# S7CAS-PLEIADES-CARTE-MERE_P06_FPGA3.net
KiCad netlist of a schematic drawn in Altium Designer
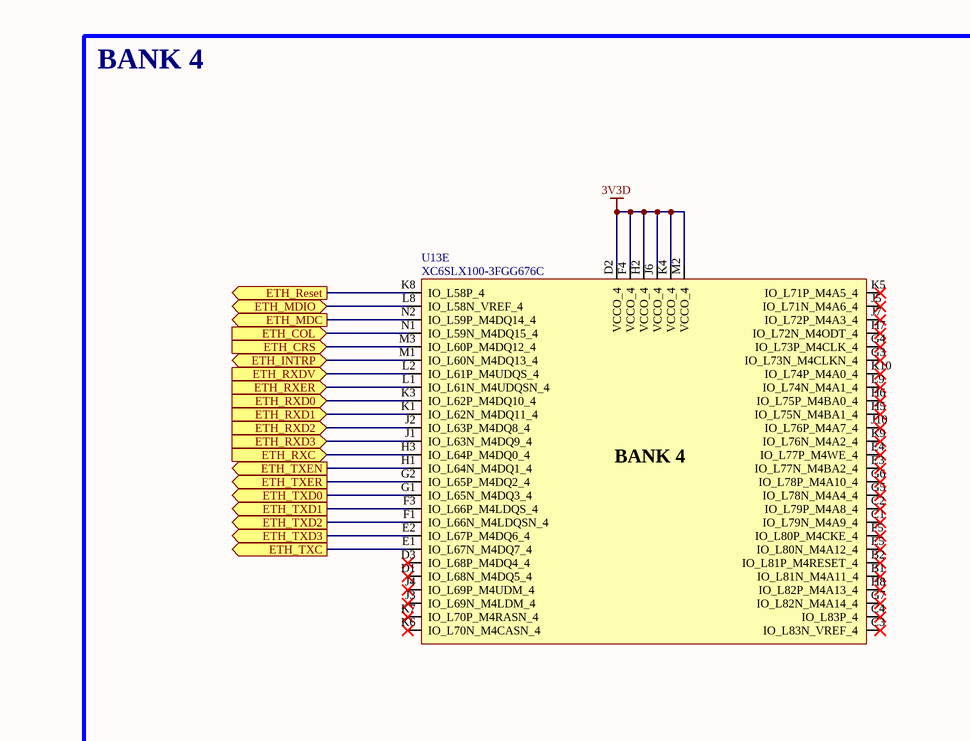
[diagram p0: S7CAS-PLEIADES-CARTE-MERE_P06_FPGA3.SCHDOC, top left]
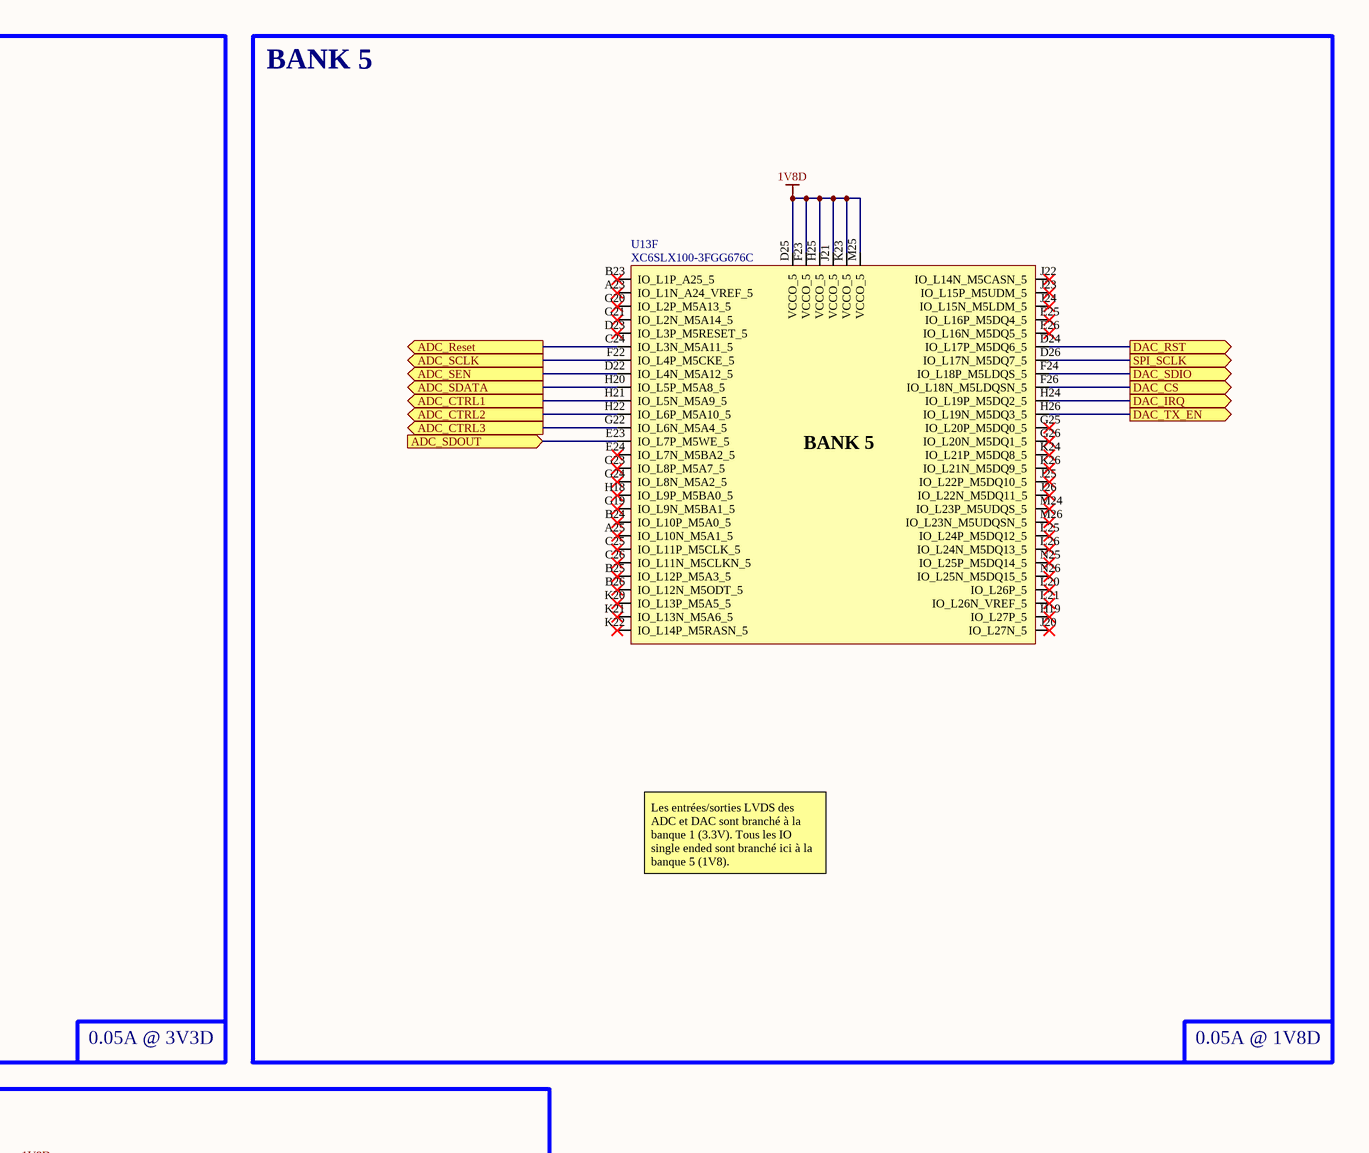
[diagram p1: S7CAS-PLEIADES-CARTE-MERE_P06_FPGA3.SCHDOC, top right]
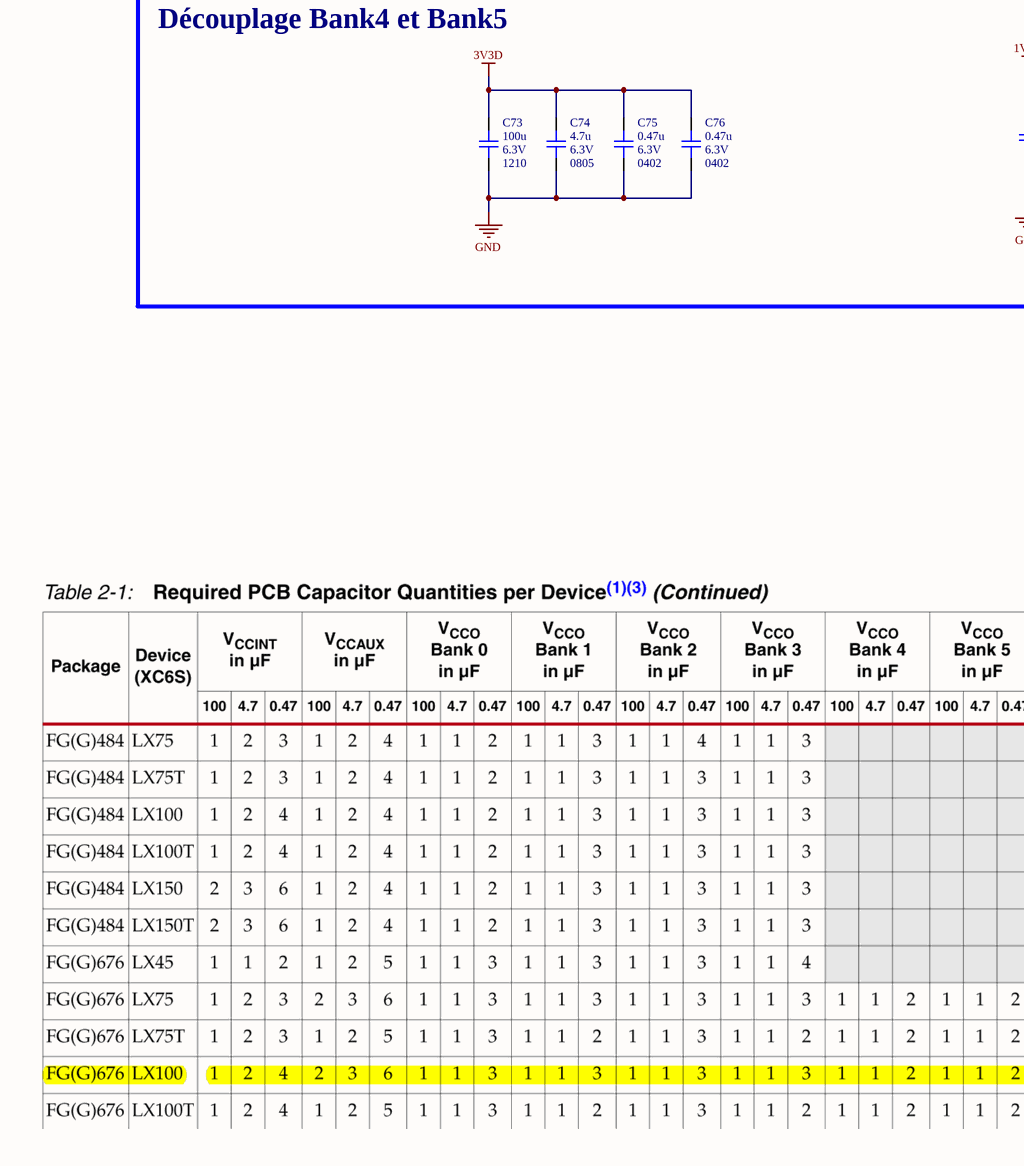
[diagram p2: S7CAS-PLEIADES-CARTE-MERE_P06_FPGA3.SCHDOC, bottom left]
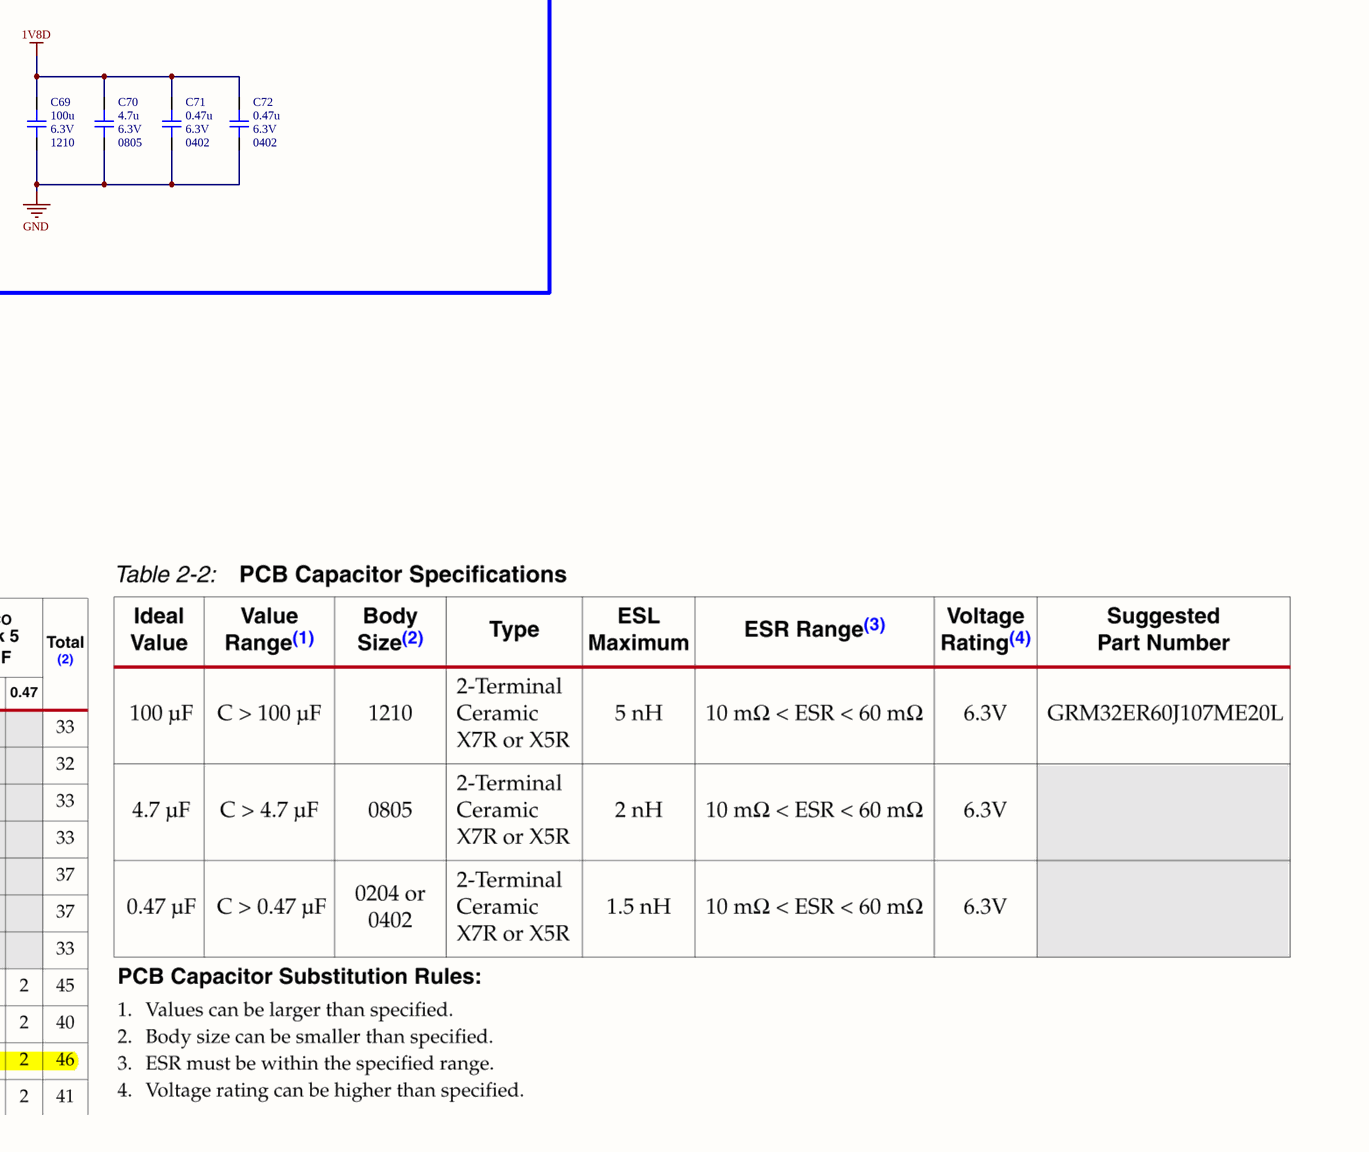
[diagram p3: S7CAS-PLEIADES-CARTE-MERE_P06_FPGA3.SCHDOC, bottom right]

(export (version "E")
  (design (tool "Eeschema 10.0.6"))
  (components
    (comp (ref "C69")
      (value "100u")
      (footprint "CAP_1210")
      (description "CAP - 1210")
      (fields
        (field (name "VOLTAGE") "6.3V")
        (field (name "PACKAGE") "1210")
        (field (name "CREATEDBY") "Jonathan Bouchard")
      )
      (libsource (lib "s7cas_lib2023") (part "CAP - 1210"))
    )
    (comp (ref "C70")
      (value "4.7u")
      (footprint "CAP_0805")
      (description "CAP - 0805")
      (fields
        (field (name "VOLTAGE") "6.3V")
        (field (name "PACKAGE") "0805")
        (field (name "CREATEDBY") "Jonathan Bouchard")
      )
      (libsource (lib "s7cas_lib2023") (part "CAP - 0805"))
    )
    (comp (ref "C71")
      (value "0.47u")
      (footprint "CAP_0402")
      (description "CAP - 0402")
      (fields
        (field (name "VOLTAGE") "6.3V")
        (field (name "PACKAGE") "0402")
        (field (name "CREATEDBY") "Jonathan Bouchard")
      )
      (libsource (lib "s7cas_lib2023") (part "CAP - 0402"))
    )
    (comp (ref "C72")
      (value "0.47u")
      (footprint "CAP_0402")
      (description "CAP - 0402")
      (fields
        (field (name "VOLTAGE") "6.3V")
        (field (name "PACKAGE") "0402")
        (field (name "CREATEDBY") "Jonathan Bouchard")
      )
      (libsource (lib "s7cas_lib2023") (part "CAP - 0402"))
    )
    (comp (ref "C73")
      (value "100u")
      (footprint "CAP_1210")
      (description "CAP - 1210")
      (fields
        (field (name "VOLTAGE") "6.3V")
        (field (name "PACKAGE") "1210")
        (field (name "CREATEDBY") "Jonathan Bouchard")
      )
      (libsource (lib "s7cas_lib2023") (part "CAP - 1210"))
    )
    (comp (ref "C74")
      (value "4.7u")
      (footprint "CAP_0805")
      (description "CAP - 0805")
      (fields
        (field (name "VOLTAGE") "6.3V")
        (field (name "PACKAGE") "0805")
        (field (name "CREATEDBY") "Jonathan Bouchard")
      )
      (libsource (lib "s7cas_lib2023") (part "CAP - 0805"))
    )
    (comp (ref "C75")
      (value "0.47u")
      (footprint "CAP_0402")
      (description "CAP - 0402")
      (fields
        (field (name "VOLTAGE") "6.3V")
        (field (name "PACKAGE") "0402")
        (field (name "CREATEDBY") "Jonathan Bouchard")
      )
      (libsource (lib "s7cas_lib2023") (part "CAP - 0402"))
    )
    (comp (ref "C76")
      (value "0.47u")
      (footprint "CAP_0402")
      (description "CAP - 0402")
      (fields
        (field (name "VOLTAGE") "6.3V")
        (field (name "PACKAGE") "0402")
        (field (name "CREATEDBY") "Jonathan Bouchard")
      )
      (libsource (lib "s7cas_lib2023") (part "CAP - 0402"))
    )
    (comp (ref "U13")
      (value "XC6SLX100-3FGG676C")
      (footprint "FPGA_XILINX_FGG676")
      (description "FPGA - XILINX SPARTAN 6 480 I/O - BGA-676")
      (fields
        (field (name "VOLTAGE") "1.14 V ~ 1.26 V")
        (field (name "MFG") "Xilinx")
        (field (name "CREATEDBY") "Jonathan Bouchard")
      )
      (libsource (lib "s7cas_lib2023") (part "FPGA_XC6SLX100-3FGG676C"))
    )
  )
  (nets
    (net (code "1") (name "/ADC_CTRL1") (class "Default")
      (node (ref "U13") (pin "H21") (pinfunction "IO_L5N_M5A9_5_H21") (pintype "passive"))
    )
    (net (code "2") (name "/ADC_CTRL2") (class "Default")
      (node (ref "U13") (pin "H22") (pinfunction "IO_L6P_M5A10_5_H22") (pintype "passive"))
    )
    (net (code "3") (name "/ADC_CTRL3") (class "Default")
      (node (ref "U13") (pin "G22") (pinfunction "IO_L6N_M5A4_5_G22") (pintype "passive"))
    )
    (net (code "4") (name "/ADC_Reset") (class "Default")
      (node (ref "U13") (pin "C24") (pinfunction "IO_L3N_M5A11_5_C24") (pintype "passive"))
    )
    (net (code "5") (name "/ADC_SCLK") (class "Default")
      (node (ref "U13") (pin "F22") (pinfunction "IO_L4P_M5CKE_5_F22") (pintype "passive"))
    )
    (net (code "6") (name "/ADC_SDATA") (class "Default")
      (node (ref "U13") (pin "H20") (pinfunction "IO_L5P_M5A8_5_H20") (pintype "passive"))
    )
    (net (code "7") (name "/ADC_SDOUT") (class "Default")
      (node (ref "U13") (pin "E23") (pinfunction "IO_L7P_M5WE_5_E23") (pintype "passive"))
    )
    (net (code "8") (name "/ADC_SEN") (class "Default")
      (node (ref "U13") (pin "D22") (pinfunction "IO_L4N_M5A12_5_D22") (pintype "passive"))
    )
    (net (code "9") (name "/DAC_CS") (class "Default")
      (node (ref "U13") (pin "F26") (pinfunction "IO_L18N_M5LDQSN_5_F26") (pintype "passive"))
    )
    (net (code "10") (name "/DAC_IRQ") (class "Default")
      (node (ref "U13") (pin "H24") (pinfunction "IO_L19P_M5DQ2_5_H24") (pintype "passive"))
    )
    (net (code "11") (name "/DAC_RST") (class "Default")
      (node (ref "U13") (pin "D24") (pinfunction "IO_L17P_M5DQ6_5_D24") (pintype "passive"))
    )
    (net (code "12") (name "/DAC_SDIO") (class "Default")
      (node (ref "U13") (pin "F24") (pinfunction "IO_L18P_M5LDQS_5_F24") (pintype "passive"))
    )
    (net (code "13") (name "/DAC_TX_EN") (class "Default")
      (node (ref "U13") (pin "H26") (pinfunction "IO_L19N_M5DQ3_5_H26") (pintype "passive"))
    )
    (net (code "14") (name "/ETH_COL") (class "Default")
      (node (ref "U13") (pin "N1") (pinfunction "IO_L59N_M4DQ15_4_N1") (pintype "passive"))
    )
    (net (code "15") (name "/ETH_CRS") (class "Default")
      (node (ref "U13") (pin "M3") (pinfunction "IO_L60P_M4DQ12_4_M3") (pintype "passive"))
    )
    (net (code "16") (name "/ETH_INTRP") (class "Default")
      (node (ref "U13") (pin "M1") (pinfunction "IO_L60N_M4DQ13_4_M1") (pintype "passive"))
    )
    (net (code "17") (name "/ETH_MDC") (class "Default")
      (node (ref "U13") (pin "N2") (pinfunction "IO_L59P_M4DQ14_4_N2") (pintype "passive"))
    )
    (net (code "18") (name "/ETH_MDIO") (class "Default")
      (node (ref "U13") (pin "L8") (pinfunction "IO_L58N_VREF_4_L8") (pintype "passive"))
    )
    (net (code "19") (name "/ETH_RXC") (class "Default")
      (node (ref "U13") (pin "H3") (pinfunction "IO_L64P_M4DQ0_4_H3") (pintype "passive"))
    )
    (net (code "20") (name "/ETH_RXD0") (class "Default")
      (node (ref "U13") (pin "K3") (pinfunction "IO_L62P_M4DQ10_4_K3") (pintype "passive"))
    )
    (net (code "21") (name "/ETH_RXD1") (class "Default")
      (node (ref "U13") (pin "K1") (pinfunction "IO_L62N_M4DQ11_4_K1") (pintype "passive"))
    )
    (net (code "22") (name "/ETH_RXD2") (class "Default")
      (node (ref "U13") (pin "J2") (pinfunction "IO_L63P_M4DQ8_4_J2") (pintype "passive"))
    )
    (net (code "23") (name "/ETH_RXD3") (class "Default")
      (node (ref "U13") (pin "J1") (pinfunction "IO_L63N_M4DQ9_4_J1") (pintype "passive"))
    )
    (net (code "24") (name "/ETH_RXDV") (class "Default")
      (node (ref "U13") (pin "L2") (pinfunction "IO_L61P_M4UDQS_4_L2") (pintype "passive"))
    )
    (net (code "25") (name "/ETH_RXER") (class "Default")
      (node (ref "U13") (pin "L1") (pinfunction "IO_L61N_M4UDQSN_4_L1") (pintype "passive"))
    )
    (net (code "26") (name "/ETH_Reset") (class "Default")
      (node (ref "U13") (pin "K8") (pinfunction "IO_L58P_4_K8") (pintype "passive"))
    )
    (net (code "27") (name "/ETH_TXC") (class "Default")
      (node (ref "U13") (pin "E1") (pinfunction "IO_L67N_M4DQ7_4_E1") (pintype "passive"))
    )
    (net (code "28") (name "/ETH_TXD0") (class "Default")
      (node (ref "U13") (pin "G1") (pinfunction "IO_L65N_M4DQ3_4_G1") (pintype "passive"))
    )
    (net (code "29") (name "/ETH_TXD1") (class "Default")
      (node (ref "U13") (pin "F3") (pinfunction "IO_L66P_M4LDQS_4_F3") (pintype "passive"))
    )
    (net (code "30") (name "/ETH_TXD2") (class "Default")
      (node (ref "U13") (pin "F1") (pinfunction "IO_L66N_M4LDQSN_4_F1") (pintype "passive"))
    )
    (net (code "31") (name "/ETH_TXD3") (class "Default")
      (node (ref "U13") (pin "E2") (pinfunction "IO_L67P_M4DQ6_4_E2") (pintype "passive"))
    )
    (net (code "32") (name "/ETH_TXEN") (class "Default")
      (node (ref "U13") (pin "H1") (pinfunction "IO_L64N_M4DQ1_4_H1") (pintype "passive"))
    )
    (net (code "33") (name "/ETH_TXER") (class "Default")
      (node (ref "U13") (pin "G2") (pinfunction "IO_L65P_M4DQ2_4_G2") (pintype "passive"))
    )
    (net (code "34") (name "/SPI_SCLK") (class "Default")
      (node (ref "U13") (pin "D26") (pinfunction "IO_L17N_M5DQ7_5_D26") (pintype "passive"))
    )
    (net (code "35") (name "1V8D") (class "Default")
      (node (ref "C69") (pin "2") (pinfunction "2_2") (pintype "passive"))
      (node (ref "C70") (pin "2") (pinfunction "2_2") (pintype "passive"))
      (node (ref "C71") (pin "2") (pinfunction "2_2") (pintype "passive"))
      (node (ref "C72") (pin "2") (pinfunction "2_2") (pintype "passive"))
      (node (ref "U13") (pin "D25") (pinfunction "VCCO_5_D25") (pintype "passive"))
      (node (ref "U13") (pin "F23") (pinfunction "VCCO_5_F23") (pintype "passive"))
      (node (ref "U13") (pin "H25") (pinfunction "VCCO_5_H25") (pintype "passive"))
      (node (ref "U13") (pin "J21") (pinfunction "VCCO_5_J21") (pintype "passive"))
      (node (ref "U13") (pin "K23") (pinfunction "VCCO_5_K23") (pintype "passive"))
      (node (ref "U13") (pin "M25") (pinfunction "VCCO_5_M25") (pintype "passive"))
    )
    (net (code "36") (name "3V3D") (class "Default")
      (node (ref "C73") (pin "2") (pinfunction "2_2") (pintype "passive"))
      (node (ref "C74") (pin "2") (pinfunction "2_2") (pintype "passive"))
      (node (ref "C75") (pin "2") (pinfunction "2_2") (pintype "passive"))
      (node (ref "C76") (pin "2") (pinfunction "2_2") (pintype "passive"))
      (node (ref "U13") (pin "D2") (pinfunction "VCCO_4_D2") (pintype "passive"))
      (node (ref "U13") (pin "F4") (pinfunction "VCCO_4_F4") (pintype "passive"))
      (node (ref "U13") (pin "H2") (pinfunction "VCCO_4_H2") (pintype "passive"))
      (node (ref "U13") (pin "J6") (pinfunction "VCCO_4_J6") (pintype "passive"))
      (node (ref "U13") (pin "K4") (pinfunction "VCCO_4_K4") (pintype "passive"))
      (node (ref "U13") (pin "M2") (pinfunction "VCCO_4_M2") (pintype "passive"))
    )
    (net (code "37") (name "GND") (class "Default")
      (node (ref "C69") (pin "1") (pinfunction "1_1") (pintype "passive"))
      (node (ref "C70") (pin "1") (pinfunction "1_1") (pintype "passive"))
      (node (ref "C71") (pin "1") (pinfunction "1_1") (pintype "passive"))
      (node (ref "C72") (pin "1") (pinfunction "1_1") (pintype "passive"))
      (node (ref "C73") (pin "1") (pinfunction "1_1") (pintype "passive"))
      (node (ref "C74") (pin "1") (pinfunction "1_1") (pintype "passive"))
      (node (ref "C75") (pin "1") (pinfunction "1_1") (pintype "passive"))
      (node (ref "C76") (pin "1") (pinfunction "1_1") (pintype "passive"))
    )
    (net (code "38") (name "unconnected-(U13E-IO_L68N_M4DQ5_4-PadD1)") (class "Default")
      (node (ref "U13") (pin "D1") (pinfunction "IO_L68N_M4DQ5_4_D1") (pintype "passive+no_connect"))
    )
    (net (code "39") (name "unconnected-(U13E-IO_L68P_M4DQ4_4-PadD3)") (class "Default")
      (node (ref "U13") (pin "D3") (pinfunction "IO_L68P_M4DQ4_4_D3") (pintype "passive+no_connect"))
    )
    (net (code "40") (name "unconnected-(U13E-IO_L69N_M4LDM_4-PadJ3)") (class "Default")
      (node (ref "U13") (pin "J3") (pinfunction "IO_L69N_M4LDM_4_J3") (pintype "passive+no_connect"))
    )
    (net (code "41") (name "unconnected-(U13E-IO_L69P_M4UDM_4-PadJ4)") (class "Default")
      (node (ref "U13") (pin "J4") (pinfunction "IO_L69P_M4UDM_4_J4") (pintype "passive+no_connect"))
    )
    (net (code "42") (name "unconnected-(U13E-IO_L70N_M4CASN_4-PadK6)") (class "Default")
      (node (ref "U13") (pin "K6") (pinfunction "IO_L70N_M4CASN_4_K6") (pintype "passive+no_connect"))
    )
    (net (code "43") (name "unconnected-(U13E-IO_L70P_M4RASN_4-PadK7)") (class "Default")
      (node (ref "U13") (pin "K7") (pinfunction "IO_L70P_M4RASN_4_K7") (pintype "passive+no_connect"))
    )
    (net (code "44") (name "unconnected-(U13E-IO_L71N_M4A6_4-PadJ5)") (class "Default")
      (node (ref "U13") (pin "J5") (pinfunction "IO_L71N_M4A6_4_J5") (pintype "passive+no_connect"))
    )
    (net (code "45") (name "unconnected-(U13E-IO_L71P_M4A5_4-PadK5)") (class "Default")
      (node (ref "U13") (pin "K5") (pinfunction "IO_L71P_M4A5_4_K5") (pintype "passive+no_connect"))
    )
    (net (code "46") (name "unconnected-(U13E-IO_L72N_M4ODT_4-PadH7)") (class "Default")
      (node (ref "U13") (pin "H7") (pinfunction "IO_L72N_M4ODT_4_H7") (pintype "passive+no_connect"))
    )
    (net (code "47") (name "unconnected-(U13E-IO_L72P_M4A3_4-PadJ7)") (class "Default")
      (node (ref "U13") (pin "J7") (pinfunction "IO_L72P_M4A3_4_J7") (pintype "passive+no_connect"))
    )
    (net (code "48") (name "unconnected-(U13E-IO_L73N_M4CLKN_4-PadG3)") (class "Default")
      (node (ref "U13") (pin "G3") (pinfunction "IO_L73N_M4CLKN_4_G3") (pintype "passive+no_connect"))
    )
    (net (code "49") (name "unconnected-(U13E-IO_L73P_M4CLK_4-PadG4)") (class "Default")
      (node (ref "U13") (pin "G4") (pinfunction "IO_L73P_M4CLK_4_G4") (pintype "passive+no_connect"))
    )
    (net (code "50") (name "unconnected-(U13E-IO_L74N_M4A1_4-PadL9)") (class "Default")
      (node (ref "U13") (pin "L9") (pinfunction "IO_L74N_M4A1_4_L9") (pintype "passive+no_connect"))
    )
    (net (code "51") (name "unconnected-(U13E-IO_L74P_M4A0_4-PadK10)") (class "Default")
      (node (ref "U13") (pin "K10") (pinfunction "IO_L74P_M4A0_4_K10") (pintype "passive+no_connect"))
    )
    (net (code "52") (name "unconnected-(U13E-IO_L75N_M4BA1_4-PadH5)") (class "Default")
      (node (ref "U13") (pin "H5") (pinfunction "IO_L75N_M4BA1_4_H5") (pintype "passive+no_connect"))
    )
    (net (code "53") (name "unconnected-(U13E-IO_L75P_M4BA0_4-PadH6)") (class "Default")
      (node (ref "U13") (pin "H6") (pinfunction "IO_L75P_M4BA0_4_H6") (pintype "passive+no_connect"))
    )
    (net (code "54") (name "unconnected-(U13E-IO_L76N_M4A2_4-PadK9)") (class "Default")
      (node (ref "U13") (pin "K9") (pinfunction "IO_L76N_M4A2_4_K9") (pintype "passive+no_connect"))
    )
    (net (code "55") (name "unconnected-(U13E-IO_L76P_M4A7_4-PadJ10)") (class "Default")
      (node (ref "U13") (pin "J10") (pinfunction "IO_L76P_M4A7_4_J10") (pintype "passive+no_connect"))
    )
    (net (code "56") (name "unconnected-(U13E-IO_L77N_M4BA2_4-PadE3)") (class "Default")
      (node (ref "U13") (pin "E3") (pinfunction "IO_L77N_M4BA2_4_E3") (pintype "passive+no_connect"))
    )
    (net (code "57") (name "unconnected-(U13E-IO_L77P_M4WE_4-PadE4)") (class "Default")
      (node (ref "U13") (pin "E4") (pinfunction "IO_L77P_M4WE_4_E4") (pintype "passive+no_connect"))
    )
    (net (code "58") (name "unconnected-(U13E-IO_L78N_M4A4_4-PadG5)") (class "Default")
      (node (ref "U13") (pin "G5") (pinfunction "IO_L78N_M4A4_4_G5") (pintype "passive+no_connect"))
    )
    (net (code "59") (name "unconnected-(U13E-IO_L78P_M4A10_4-PadG6)") (class "Default")
      (node (ref "U13") (pin "G6") (pinfunction "IO_L78P_M4A10_4_G6") (pintype "passive+no_connect"))
    )
    (net (code "60") (name "unconnected-(U13E-IO_L79N_M4A9_4-PadC1)") (class "Default")
      (node (ref "U13") (pin "C1") (pinfunction "IO_L79N_M4A9_4_C1") (pintype "passive+no_connect"))
    )
    (net (code "61") (name "unconnected-(U13E-IO_L79P_M4A8_4-PadC2)") (class "Default")
      (node (ref "U13") (pin "C2") (pinfunction "IO_L79P_M4A8_4_C2") (pintype "passive+no_connect"))
    )
    (net (code "62") (name "unconnected-(U13E-IO_L80N_M4A12_4-PadE5)") (class "Default")
      (node (ref "U13") (pin "E5") (pinfunction "IO_L80N_M4A12_4_E5") (pintype "passive+no_connect"))
    )
    (net (code "63") (name "unconnected-(U13E-IO_L80P_M4CKE_4-PadF5)") (class "Default")
      (node (ref "U13") (pin "F5") (pinfunction "IO_L80P_M4CKE_4_F5") (pintype "passive+no_connect"))
    )
    (net (code "64") (name "unconnected-(U13E-IO_L81N_M4A11_4-PadB1)") (class "Default")
      (node (ref "U13") (pin "B1") (pinfunction "IO_L81N_M4A11_4_B1") (pintype "passive+no_connect"))
    )
    (net (code "65") (name "unconnected-(U13E-IO_L81P_M4RESET_4-PadB2)") (class "Default")
      (node (ref "U13") (pin "B2") (pinfunction "IO_L81P_M4RESET_4_B2") (pintype "passive+no_connect"))
    )
    (net (code "66") (name "unconnected-(U13E-IO_L82N_M4A14_4-PadG7)") (class "Default")
      (node (ref "U13") (pin "G7") (pinfunction "IO_L82N_M4A14_4_G7") (pintype "passive+no_connect"))
    )
    (net (code "67") (name "unconnected-(U13E-IO_L82P_M4A13_4-PadH8)") (class "Default")
      (node (ref "U13") (pin "H8") (pinfunction "IO_L82P_M4A13_4_H8") (pintype "passive+no_connect"))
    )
    (net (code "68") (name "unconnected-(U13E-IO_L83N_VREF_4-PadC3)") (class "Default")
      (node (ref "U13") (pin "C3") (pinfunction "IO_L83N_VREF_4_C3") (pintype "passive+no_connect"))
    )
    (net (code "69") (name "unconnected-(U13E-IO_L83P_4-PadC4)") (class "Default")
      (node (ref "U13") (pin "C4") (pinfunction "IO_L83P_4_C4") (pintype "passive+no_connect"))
    )
    (net (code "70") (name "unconnected-(U13F-IO_L1N_A24_VREF_5-PadA23)") (class "Default")
      (node (ref "U13") (pin "A23") (pinfunction "IO_L1N_A24_VREF_5_A23") (pintype "passive+no_connect"))
    )
    (net (code "71") (name "unconnected-(U13F-IO_L1P_A25_5-PadB23)") (class "Default")
      (node (ref "U13") (pin "B23") (pinfunction "IO_L1P_A25_5_B23") (pintype "passive+no_connect"))
    )
    (net (code "72") (name "unconnected-(U13F-IO_L2N_M5A14_5-PadG21)") (class "Default")
      (node (ref "U13") (pin "G21") (pinfunction "IO_L2N_M5A14_5_G21") (pintype "passive+no_connect"))
    )
    (net (code "73") (name "unconnected-(U13F-IO_L2P_M5A13_5-PadG20)") (class "Default")
      (node (ref "U13") (pin "G20") (pinfunction "IO_L2P_M5A13_5_G20") (pintype "passive+no_connect"))
    )
    (net (code "74") (name "unconnected-(U13F-IO_L3P_M5RESET_5-PadD23)") (class "Default")
      (node (ref "U13") (pin "D23") (pinfunction "IO_L3P_M5RESET_5_D23") (pintype "passive+no_connect"))
    )
    (net (code "75") (name "unconnected-(U13F-IO_L7N_M5BA2_5-PadE24)") (class "Default")
      (node (ref "U13") (pin "E24") (pinfunction "IO_L7N_M5BA2_5_E24") (pintype "passive+no_connect"))
    )
    (net (code "76") (name "unconnected-(U13F-IO_L8N_M5A2_5-PadG24)") (class "Default")
      (node (ref "U13") (pin "G24") (pinfunction "IO_L8N_M5A2_5_G24") (pintype "passive+no_connect"))
    )
    (net (code "77") (name "unconnected-(U13F-IO_L8P_M5A7_5-PadG23)") (class "Default")
      (node (ref "U13") (pin "G23") (pinfunction "IO_L8P_M5A7_5_G23") (pintype "passive+no_connect"))
    )
    (net (code "78") (name "unconnected-(U13F-IO_L9N_M5BA1_5-PadG19)") (class "Default")
      (node (ref "U13") (pin "G19") (pinfunction "IO_L9N_M5BA1_5_G19") (pintype "passive+no_connect"))
    )
    (net (code "79") (name "unconnected-(U13F-IO_L9P_M5BA0_5-PadH18)") (class "Default")
      (node (ref "U13") (pin "H18") (pinfunction "IO_L9P_M5BA0_5_H18") (pintype "passive+no_connect"))
    )
    (net (code "80") (name "unconnected-(U13F-IO_L10N_M5A1_5-PadA25)") (class "Default")
      (node (ref "U13") (pin "A25") (pinfunction "IO_L10N_M5A1_5_A25") (pintype "passive+no_connect"))
    )
    (net (code "81") (name "unconnected-(U13F-IO_L10P_M5A0_5-PadB24)") (class "Default")
      (node (ref "U13") (pin "B24") (pinfunction "IO_L10P_M5A0_5_B24") (pintype "passive+no_connect"))
    )
    (net (code "82") (name "unconnected-(U13F-IO_L11N_M5CLKN_5-PadC26)") (class "Default")
      (node (ref "U13") (pin "C26") (pinfunction "IO_L11N_M5CLKN_5_C26") (pintype "passive+no_connect"))
    )
    (net (code "83") (name "unconnected-(U13F-IO_L11P_M5CLK_5-PadC25)") (class "Default")
      (node (ref "U13") (pin "C25") (pinfunction "IO_L11P_M5CLK_5_C25") (pintype "passive+no_connect"))
    )
    (net (code "84") (name "unconnected-(U13F-IO_L12N_M5ODT_5-PadB26)") (class "Default")
      (node (ref "U13") (pin "B26") (pinfunction "IO_L12N_M5ODT_5_B26") (pintype "passive+no_connect"))
    )
    (net (code "85") (name "unconnected-(U13F-IO_L12P_M5A3_5-PadB25)") (class "Default")
      (node (ref "U13") (pin "B25") (pinfunction "IO_L12P_M5A3_5_B25") (pintype "passive+no_connect"))
    )
    (net (code "86") (name "unconnected-(U13F-IO_L13N_M5A6_5-PadK21)") (class "Default")
      (node (ref "U13") (pin "K21") (pinfunction "IO_L13N_M5A6_5_K21") (pintype "passive+no_connect"))
    )
    (net (code "87") (name "unconnected-(U13F-IO_L13P_M5A5_5-PadK20)") (class "Default")
      (node (ref "U13") (pin "K20") (pinfunction "IO_L13P_M5A5_5_K20") (pintype "passive+no_connect"))
    )
    (net (code "88") (name "unconnected-(U13F-IO_L14N_M5CASN_5-PadJ22)") (class "Default")
      (node (ref "U13") (pin "J22") (pinfunction "IO_L14N_M5CASN_5_J22") (pintype "passive+no_connect"))
    )
    (net (code "89") (name "unconnected-(U13F-IO_L14P_M5RASN_5-PadK22)") (class "Default")
      (node (ref "U13") (pin "K22") (pinfunction "IO_L14P_M5RASN_5_K22") (pintype "passive+no_connect"))
    )
    (net (code "90") (name "unconnected-(U13F-IO_L15N_M5LDM_5-PadJ24)") (class "Default")
      (node (ref "U13") (pin "J24") (pinfunction "IO_L15N_M5LDM_5_J24") (pintype "passive+no_connect"))
    )
    (net (code "91") (name "unconnected-(U13F-IO_L15P_M5UDM_5-PadJ23)") (class "Default")
      (node (ref "U13") (pin "J23") (pinfunction "IO_L15P_M5UDM_5_J23") (pintype "passive+no_connect"))
    )
    (net (code "92") (name "unconnected-(U13F-IO_L16N_M5DQ5_5-PadE26)") (class "Default")
      (node (ref "U13") (pin "E26") (pinfunction "IO_L16N_M5DQ5_5_E26") (pintype "passive+no_connect"))
    )
    (net (code "93") (name "unconnected-(U13F-IO_L16P_M5DQ4_5-PadE25)") (class "Default")
      (node (ref "U13") (pin "E25") (pinfunction "IO_L16P_M5DQ4_5_E25") (pintype "passive+no_connect"))
    )
    (net (code "94") (name "unconnected-(U13F-IO_L20N_M5DQ1_5-PadG26)") (class "Default")
      (node (ref "U13") (pin "G26") (pinfunction "IO_L20N_M5DQ1_5_G26") (pintype "passive+no_connect"))
    )
    (net (code "95") (name "unconnected-(U13F-IO_L20P_M5DQ0_5-PadG25)") (class "Default")
      (node (ref "U13") (pin "G25") (pinfunction "IO_L20P_M5DQ0_5_G25") (pintype "passive+no_connect"))
    )
    (net (code "96") (name "unconnected-(U13F-IO_L21N_M5DQ9_5-PadK26)") (class "Default")
      (node (ref "U13") (pin "K26") (pinfunction "IO_L21N_M5DQ9_5_K26") (pintype "passive+no_connect"))
    )
    (net (code "97") (name "unconnected-(U13F-IO_L21P_M5DQ8_5-PadK24)") (class "Default")
      (node (ref "U13") (pin "K24") (pinfunction "IO_L21P_M5DQ8_5_K24") (pintype "passive+no_connect"))
    )
    (net (code "98") (name "unconnected-(U13F-IO_L22N_M5DQ11_5-PadJ26)") (class "Default")
      (node (ref "U13") (pin "J26") (pinfunction "IO_L22N_M5DQ11_5_J26") (pintype "passive+no_connect"))
    )
    (net (code "99") (name "unconnected-(U13F-IO_L22P_M5DQ10_5-PadJ25)") (class "Default")
      (node (ref "U13") (pin "J25") (pinfunction "IO_L22P_M5DQ10_5_J25") (pintype "passive+no_connect"))
    )
    (net (code "100") (name "unconnected-(U13F-IO_L23N_M5UDQSN_5-PadM26)") (class "Default")
      (node (ref "U13") (pin "M26") (pinfunction "IO_L23N_M5UDQSN_5_M26") (pintype "passive+no_connect"))
    )
    (net (code "101") (name "unconnected-(U13F-IO_L23P_M5UDQS_5-PadM24)") (class "Default")
      (node (ref "U13") (pin "M24") (pinfunction "IO_L23P_M5UDQS_5_M24") (pintype "passive+no_connect"))
    )
    (net (code "102") (name "unconnected-(U13F-IO_L24N_M5DQ13_5-PadL26)") (class "Default")
      (node (ref "U13") (pin "L26") (pinfunction "IO_L24N_M5DQ13_5_L26") (pintype "passive+no_connect"))
    )
    (net (code "103") (name "unconnected-(U13F-IO_L24P_M5DQ12_5-PadL25)") (class "Default")
      (node (ref "U13") (pin "L25") (pinfunction "IO_L24P_M5DQ12_5_L25") (pintype "passive+no_connect"))
    )
    (net (code "104") (name "unconnected-(U13F-IO_L25N_M5DQ15_5-PadN26)") (class "Default")
      (node (ref "U13") (pin "N26") (pinfunction "IO_L25N_M5DQ15_5_N26") (pintype "passive+no_connect"))
    )
    (net (code "105") (name "unconnected-(U13F-IO_L25P_M5DQ14_5-PadN25)") (class "Default")
      (node (ref "U13") (pin "N25") (pinfunction "IO_L25P_M5DQ14_5_N25") (pintype "passive+no_connect"))
    )
    (net (code "106") (name "unconnected-(U13F-IO_L26N_VREF_5-PadL21)") (class "Default")
      (node (ref "U13") (pin "L21") (pinfunction "IO_L26N_VREF_5_L21") (pintype "passive+no_connect"))
    )
    (net (code "107") (name "unconnected-(U13F-IO_L26P_5-PadL20)") (class "Default")
      (node (ref "U13") (pin "L20") (pinfunction "IO_L26P_5_L20") (pintype "passive+no_connect"))
    )
    (net (code "108") (name "unconnected-(U13F-IO_L27N_5-PadJ20)") (class "Default")
      (node (ref "U13") (pin "J20") (pinfunction "IO_L27N_5_J20") (pintype "passive+no_connect"))
    )
    (net (code "109") (name "unconnected-(U13F-IO_L27P_5-PadH19)") (class "Default")
      (node (ref "U13") (pin "H19") (pinfunction "IO_L27P_5_H19") (pintype "passive+no_connect"))
    )
  )
)
